# 14_8V-5V-Buck_test.net
KiCad netlist of a schematic drawn in Altium Designer
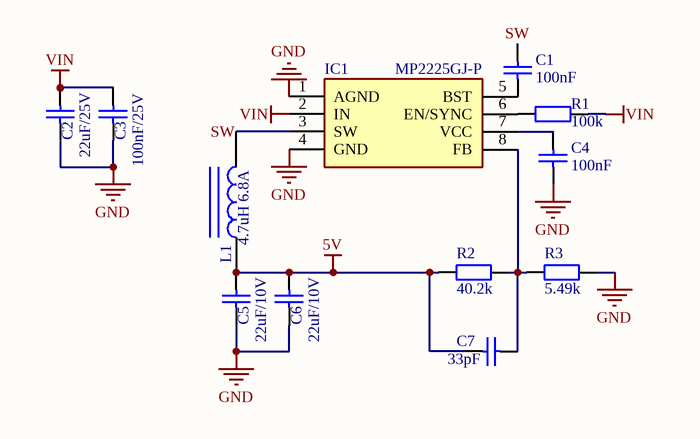
[diagram p0: 14.8V-5V-Buck_test.SchDoc]

(export (version "E")
  (design (tool "Eeschema 10.0.6"))
  (components
    (comp (ref "C1")
      (value "100nF")
      (footprint "CAP-0603")
      (description "贴片电容")
      (libsource (lib "Power_Lib_Altium") (part "CAP"))
    )
    (comp (ref "C2")
      (value "22uF/25V")
      (footprint "CAP-0603")
      (description "贴片电容")
      (libsource (lib "Power_Lib_Altium") (part "CAP"))
    )
    (comp (ref "C3")
      (value "100nF/25V")
      (footprint "CAP-0603")
      (description "贴片电容")
      (libsource (lib "Power_Lib_Altium") (part "CAP"))
    )
    (comp (ref "C4")
      (value "100nF")
      (footprint "CAP-0603")
      (description "贴片电容")
      (libsource (lib "Power_Lib_Altium") (part "CAP"))
    )
    (comp (ref "C5")
      (value "22uF/10V")
      (footprint "CAP-0603")
      (description "贴片电容")
      (libsource (lib "Power_Lib_Altium") (part "CAP"))
    )
    (comp (ref "C6")
      (value "22uF/10V")
      (footprint "CAP-0603")
      (description "贴片电容")
      (libsource (lib "Power_Lib_Altium") (part "CAP"))
    )
    (comp (ref "C7")
      (value "33pF")
      (footprint "CAP-0603")
      (description "贴片电容")
      (libsource (lib "Power_Lib_Altium") (part "CAP"))
    )
    (comp (ref "IC1")
      (value "MP2225GJ-P")
      (footprint "TSOT-23-8")
      (description "Switching Voltage Regulators HighEfficiency5A 18V Sync Step Down Conv")
      (fields (field (name "MOUSER PART NUMBER") "946-MP2225GJ-P"))
      (libsource (lib "Power_Lib_Altium") (part "MP2225GJ-P"))
    )
    (comp (ref "L1")
      (value "4.7uH 6.8A")
      (footprint "XAL6060-103MEB")
      (description "电感")
      (libsource (lib "Power_Lib_Altium") (part "INDUCTOR"))
    )
    (comp (ref "R1")
      (value "100k")
      (footprint "R-0603")
      (description "贴片电阻")
      (libsource (lib "Power_Lib_Altium") (part "RES"))
    )
    (comp (ref "R2")
      (value "40.2k")
      (footprint "R-0603")
      (description "贴片电阻")
      (libsource (lib "Power_Lib_Altium") (part "RES"))
    )
    (comp (ref "R3")
      (value "5.49k")
      (footprint "R-0603")
      (description "贴片电阻")
      (libsource (lib "Power_Lib_Altium") (part "RES"))
    )
  )
  (nets
    (net (code "1") (name "/SW") (class "Default")
      (node (ref "C1") (pin "1") (pinfunction "1_1") (pintype "passive"))
      (node (ref "IC1") (pin "3") (pinfunction "SW_3") (pintype "passive"))
      (node (ref "L1") (pin "2") (pinfunction "2_2") (pintype "passive"))
    )
    (net (code "2") (name "5V") (class "Default")
      (node (ref "C5") (pin "2") (pinfunction "2_2") (pintype "passive"))
      (node (ref "C6") (pin "2") (pinfunction "2_2") (pintype "passive"))
      (node (ref "C7") (pin "2") (pinfunction "2_2") (pintype "passive"))
      (node (ref "L1") (pin "1") (pinfunction "1_1") (pintype "passive"))
      (node (ref "R2") (pin "2") (pinfunction "2_2") (pintype "passive"))
    )
    (net (code "3") (name "GND") (class "Default")
      (node (ref "C2") (pin "1") (pinfunction "1_1") (pintype "passive"))
      (node (ref "C3") (pin "1") (pinfunction "1_1") (pintype "passive"))
      (node (ref "C4") (pin "1") (pinfunction "1_1") (pintype "passive"))
      (node (ref "C5") (pin "1") (pinfunction "1_1") (pintype "passive"))
      (node (ref "C6") (pin "1") (pinfunction "1_1") (pintype "passive"))
      (node (ref "IC1") (pin "1") (pinfunction "AGND_1") (pintype "passive"))
      (node (ref "IC1") (pin "4") (pinfunction "GND_4") (pintype "passive"))
      (node (ref "R3") (pin "1") (pinfunction "1_1") (pintype "passive"))
    )
    (net (code "4") (name "Net-(IC1-BST)") (class "Default")
      (node (ref "C1") (pin "2") (pinfunction "2_2") (pintype "passive"))
      (node (ref "IC1") (pin "5") (pinfunction "BST_5") (pintype "passive"))
    )
    (net (code "5") (name "Net-(IC1-EN{slash}SYNC)") (class "Default")
      (node (ref "IC1") (pin "6") (pinfunction "EN/SYNC_6") (pintype "passive"))
      (node (ref "R1") (pin "2") (pinfunction "2_2") (pintype "passive"))
    )
    (net (code "6") (name "Net-(IC1-FB)") (class "Default")
      (node (ref "C7") (pin "1") (pinfunction "1_1") (pintype "passive"))
      (node (ref "IC1") (pin "8") (pinfunction "FB_8") (pintype "passive"))
      (node (ref "R2") (pin "1") (pinfunction "1_1") (pintype "passive"))
      (node (ref "R3") (pin "2") (pinfunction "2_2") (pintype "passive"))
    )
    (net (code "7") (name "Net-(IC1-VCC)") (class "Default")
      (node (ref "C4") (pin "2") (pinfunction "2_2") (pintype "passive"))
      (node (ref "IC1") (pin "7") (pinfunction "VCC_7") (pintype "passive"))
    )
    (net (code "8") (name "VIN") (class "Default")
      (node (ref "C2") (pin "2") (pinfunction "2_2") (pintype "passive"))
      (node (ref "C3") (pin "2") (pinfunction "2_2") (pintype "passive"))
      (node (ref "IC1") (pin "2") (pinfunction "IN_2") (pintype "passive"))
      (node (ref "R1") (pin "1") (pinfunction "1_1") (pintype "passive"))
    )
  )
)
